# encoder_debounce.net
KiCad netlist of a schematic drawn in EAGLE
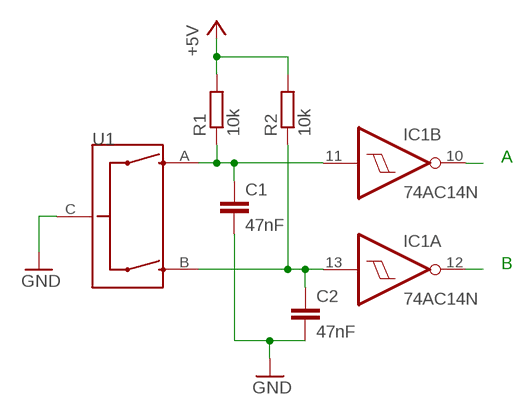
[diagram p0: schematic, sheet 1]

(export (version "E")
  (design (tool "Eeschema 10.0.6"))
  (components
    (comp (ref "C1")
      (value "47nF")
      (footprint "eagle-import:C025-050X050")
      (libsource (lib "eagle-import") (part "C-EU025-050X050"))
    )
    (comp (ref "C2")
      (value "47nF")
      (footprint "eagle-import:C025-050X050")
      (libsource (lib "eagle-import") (part "C-EU025-050X050"))
    )
    (comp (ref "IC1")
      (value "74AC14N")
      (footprint "eagle-import:DIL14")
      (libsource (lib "eagle-import") (part "7414NAC"))
    )
    (comp (ref "R1")
      (value "10k")
      (footprint "eagle-import:0207_12")
      (libsource (lib "eagle-import") (part "R-EU_0207/12"))
    )
    (comp (ref "R2")
      (value "10k")
      (footprint "eagle-import:0207_12")
      (libsource (lib "eagle-import") (part "R-EU_0207/12"))
    )
    (comp (ref "U1")
      (value "ENCODER-QUADRATURE")
      (footprint "eagle-import:ENCODER-16MM-QUAD")
      (libsource (lib "eagle-import") (part "ENCODER-QUADRATURE"))
    )
  )
  (nets
    (net (code "1") (name "+5V") (class "Default")
      (node (ref "R1") (pin "2") (pinfunction "2_2") (pintype "passive"))
      (node (ref "R2") (pin "2") (pinfunction "2_2") (pintype "passive"))
    )
    (net (code "2") (name "GND") (class "Default")
      (node (ref "C1") (pin "2") (pinfunction "2_2") (pintype "passive"))
      (node (ref "C2") (pin "2") (pinfunction "2_2") (pintype "passive"))
      (node (ref "U1") (pin "C") (pinfunction "C_C") (pintype "bidirectional"))
    )
    (net (code "3") (name "Net-(IC1A-I)") (class "Default")
      (node (ref "C2") (pin "1") (pinfunction "1_1") (pintype "passive"))
      (node (ref "IC1") (pin "13") (pinfunction "I_13") (pintype "input"))
      (node (ref "R2") (pin "1") (pinfunction "1_1") (pintype "passive"))
      (node (ref "U1") (pin "B") (pinfunction "B_B") (pintype "bidirectional"))
    )
    (net (code "4") (name "Net-(IC1B-I)") (class "Default")
      (node (ref "C1") (pin "1") (pinfunction "1_1") (pintype "passive"))
      (node (ref "IC1") (pin "11") (pinfunction "I_11") (pintype "input"))
      (node (ref "R1") (pin "1") (pinfunction "1_1") (pintype "passive"))
      (node (ref "U1") (pin "A") (pinfunction "A_A") (pintype "bidirectional"))
    )
    (net (code "5") (name "unconnected-(IC1A-O-Pad12)") (class "Default")
      (node (ref "IC1") (pin "12") (pinfunction "O_12") (pintype "output"))
    )
    (net (code "6") (name "unconnected-(IC1B-O-Pad10)") (class "Default")
      (node (ref "IC1") (pin "10") (pinfunction "O_10") (pintype "output"))
    )
  )
)
